# InputAmplifier.net
KiCad netlist of a schematic drawn in Altium Designer
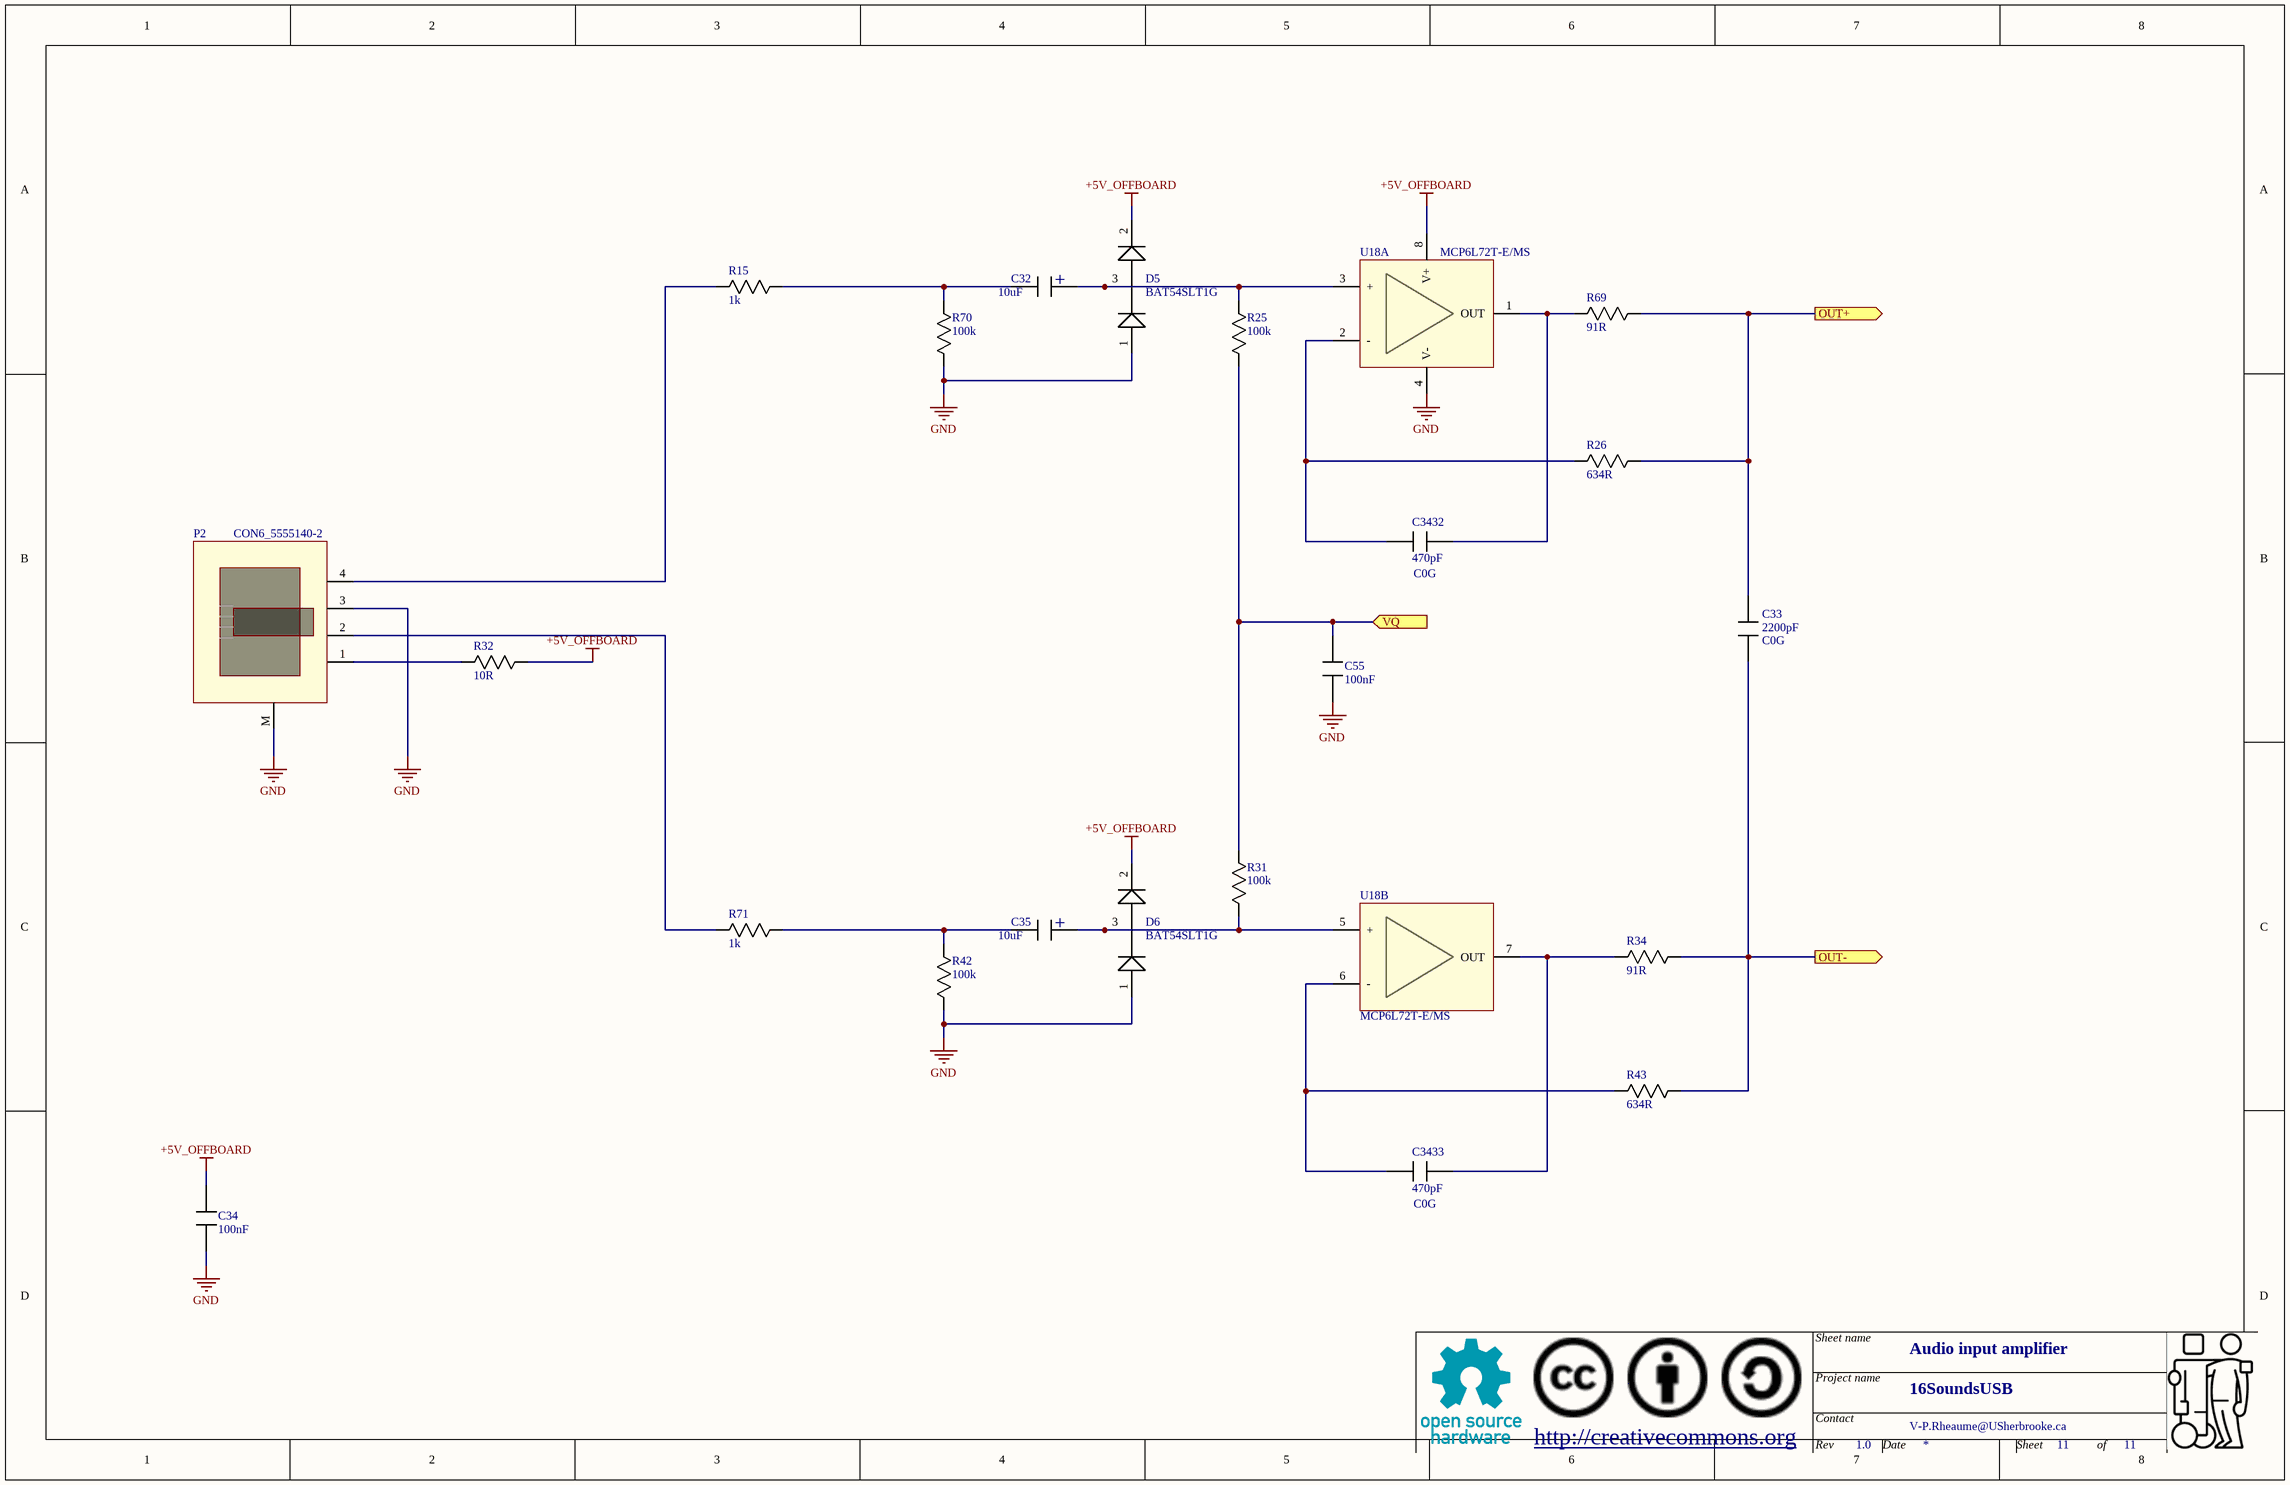
[diagram p0: InputAmplifier.SchDoc]

(export (version "E")
  (design (tool "Eeschema 10.0.6"))
  (components
    (comp (ref "C32")
      (value "10uF")
      (footprint "CAP_RAD_SMD_DIA157")
      (description "Capacitor")
      (fields (field (name "MFG") "Nichicon") (field (name "Comment") "Capacitor_Polarized"))
      (libsource (lib "INTER_2014") (part "Capacitor_Polarized"))
    )
    (comp (ref "C33")
      (value "2200pF")
      (footprint "0603")
      (description "Capacitor")
      (fields (field (name "MFG") "Murata") (field (name "TYPE") "C0G"))
      (libsource (lib "INTER_2014") (part "Capacitor"))
    )
    (comp (ref "C34")
      (value "100nF")
      (footprint "0603")
      (description "Capacitor")
      (fields (field (name "MFG") "Samsung"))
      (libsource (lib "INTER_2014") (part "Capacitor"))
    )
    (comp (ref "C35")
      (value "10uF")
      (footprint "CAP_RAD_SMD_DIA157")
      (description "Capacitor")
      (fields (field (name "MFG") "Nichicon") (field (name "Comment") "Capacitor_Polarized"))
      (libsource (lib "INTER_2014") (part "Capacitor_Polarized"))
    )
    (comp (ref "C55")
      (value "100nF")
      (footprint "0603")
      (description "Capacitor")
      (fields (field (name "MFG") "Samsung"))
      (libsource (lib "INTER_2014") (part "Capacitor"))
    )
    (comp (ref "C3432")
      (value "470pF")
      (footprint "0603")
      (description "Capacitor")
      (fields (field (name "MFG") "Samsung") (field (name "TYPE") "C0G"))
      (libsource (lib "INTER_2014") (part "Capacitor"))
    )
    (comp (ref "C3433")
      (value "470pF")
      (footprint "0603")
      (description "Capacitor")
      (fields (field (name "MFG") "Samsung") (field (name "TYPE") "C0G"))
      (libsource (lib "INTER_2014") (part "Capacitor"))
    )
    (comp (ref "D5")
      (value "Diode_dual")
      (footprint "SOT23_132")
      (description "Diode")
      (fields (field (name "MFG") "Onsemi") (field (name "MFG_PN") "BAT54SLT1G"))
      (libsource (lib "INTER_2014") (part "Diode_dual"))
    )
    (comp (ref "D6")
      (value "Diode_dual")
      (footprint "SOT23_132")
      (description "Diode")
      (fields (field (name "MFG") "Onsemi") (field (name "MFG_PN") "BAT54SLT1G"))
      (libsource (lib "INTER_2014") (part "Diode_dual"))
    )
    (comp (ref "P2")
      (value "CON6_5555140-2")
      (footprint "CONN4_5555140-2")
      (description "6p4c RJ11/RJ14, shielded (5555165-2 unshielded)")
      (fields (field (name "MFG") "TE"))
      (libsource (lib "INTER_2014") (part "CON6_5555140-2"))
    )
    (comp (ref "R15")
      (value "1k")
      (footprint "0603")
      (description "Resistor")
      (fields (field (name "MFG") "Yageo"))
      (libsource (lib "INTER_2014") (part "Resistor"))
    )
    (comp (ref "R25")
      (value "100k")
      (footprint "0603")
      (description "Resistor")
      (fields (field (name "MFG") "Yageo"))
      (libsource (lib "INTER_2014") (part "Resistor"))
    )
    (comp (ref "R26")
      (value "634R")
      (footprint "0603")
      (description "Resistor")
      (fields (field (name "MFG") "Yageo"))
      (libsource (lib "INTER_2014") (part "Resistor"))
    )
    (comp (ref "R31")
      (value "100k")
      (footprint "0603")
      (description "Resistor")
      (fields (field (name "MFG") "Yageo"))
      (libsource (lib "INTER_2014") (part "Resistor"))
    )
    (comp (ref "R32")
      (value "10R")
      (footprint "0603")
      (description "Resistor")
      (fields (field (name "MFG") "Yageo"))
      (libsource (lib "INTER_2014") (part "Resistor"))
    )
    (comp (ref "R34")
      (value "91R")
      (footprint "0603")
      (description "Resistor")
      (fields (field (name "MFG") "Yageo"))
      (libsource (lib "INTER_2014") (part "Resistor"))
    )
    (comp (ref "R42")
      (value "100k")
      (footprint "0603")
      (description "Resistor")
      (fields (field (name "MFG") "Yageo"))
      (libsource (lib "INTER_2014") (part "Resistor"))
    )
    (comp (ref "R43")
      (value "634R")
      (footprint "0603")
      (description "Resistor")
      (fields (field (name "MFG") "Yageo"))
      (libsource (lib "INTER_2014") (part "Resistor"))
    )
    (comp (ref "R69")
      (value "91R")
      (footprint "0603")
      (description "Resistor")
      (fields (field (name "MFG") "Yageo"))
      (libsource (lib "INTER_2014") (part "Resistor"))
    )
    (comp (ref "R70")
      (value "100k")
      (footprint "0603")
      (description "Resistor")
      (fields (field (name "MFG") "Yageo"))
      (libsource (lib "INTER_2014") (part "Resistor"))
    )
    (comp (ref "R71")
      (value "1k")
      (footprint "0603")
      (description "Resistor")
      (fields (field (name "MFG") "Yageo"))
      (libsource (lib "INTER_2014") (part "Resistor"))
    )
    (comp (ref "U18")
      (value "OPA_DUAL")
      (footprint "SOP127P600-8N")
      (description "Dual amplifier (standard)")
      (fields (field (name "MFG") "Microchip") (field (name "MFG_PN") "MCP6L72T-E/MS"))
      (libsource (lib "INTER_2014") (part "OPA_DUAL"))
    )
  )
  (nets
    (net (code "1") (name "+5V_OFFBOARD") (class "Default")
      (node (ref "C34") (pin "1") (pintype "passive"))
      (node (ref "D5") (pin "2") (pinfunction "K_2") (pintype "passive"))
      (node (ref "D6") (pin "2") (pinfunction "K_2") (pintype "passive"))
      (node (ref "R32") (pin "2") (pintype "passive"))
      (node (ref "U18") (pin "8") (pinfunction "V+_8") (pintype "passive"))
    )
    (net (code "2") (name "/OUT+") (class "Default")
      (node (ref "C33") (pin "1") (pintype "passive"))
      (node (ref "R26") (pin "2") (pintype "passive"))
      (node (ref "R69") (pin "2") (pintype "passive"))
    )
    (net (code "3") (name "/OUT-") (class "Default")
      (node (ref "C33") (pin "2") (pintype "passive"))
      (node (ref "R34") (pin "2") (pintype "passive"))
      (node (ref "R43") (pin "2") (pintype "passive"))
    )
    (net (code "4") (name "/VQ") (class "Default")
      (node (ref "C55") (pin "1") (pintype "passive"))
      (node (ref "R25") (pin "1") (pintype "passive"))
      (node (ref "R31") (pin "2") (pintype "passive"))
    )
    (net (code "5") (name "GND") (class "Default")
      (node (ref "C34") (pin "2") (pintype "passive"))
      (node (ref "C55") (pin "2") (pintype "passive"))
      (node (ref "D5") (pin "1") (pinfunction "K_1") (pintype "passive"))
      (node (ref "D6") (pin "1") (pinfunction "K_1") (pintype "passive"))
      (node (ref "P2") (pin "3") (pintype "passive"))
      (node (ref "P2") (pin "M") (pintype "passive"))
      (node (ref "R42") (pin "1") (pintype "passive"))
      (node (ref "R70") (pin "1") (pintype "passive"))
      (node (ref "U18") (pin "4") (pinfunction "V-_4") (pintype "passive"))
    )
    (net (code "6") (name "Net-(C32-Pad-)") (class "Default")
      (node (ref "C32") (pin "-") (pintype "passive"))
      (node (ref "R15") (pin "2") (pintype "passive"))
      (node (ref "R70") (pin "2") (pintype "passive"))
    )
    (net (code "7") (name "Net-(C35-Pad-)") (class "Default")
      (node (ref "C35") (pin "-") (pintype "passive"))
      (node (ref "R42") (pin "2") (pintype "passive"))
      (node (ref "R71") (pin "2") (pintype "passive"))
    )
    (net (code "8") (name "Net-(D5-AK)") (class "Default")
      (node (ref "C32") (pin "+") (pintype "passive"))
      (node (ref "D5") (pin "3") (pinfunction "AK_3") (pintype "passive"))
      (node (ref "R25") (pin "2") (pintype "passive"))
      (node (ref "U18") (pin "3") (pinfunction "+_3") (pintype "passive"))
    )
    (net (code "9") (name "Net-(D6-AK)") (class "Default")
      (node (ref "C35") (pin "+") (pintype "passive"))
      (node (ref "D6") (pin "3") (pinfunction "AK_3") (pintype "passive"))
      (node (ref "R31") (pin "1") (pintype "passive"))
      (node (ref "U18") (pin "5") (pinfunction "+_5") (pintype "passive"))
    )
    (net (code "10") (name "Net-(P2-Pad1)") (class "Default")
      (node (ref "P2") (pin "1") (pintype "passive"))
      (node (ref "R32") (pin "1") (pintype "passive"))
    )
    (net (code "11") (name "Net-(P2-Pad2)") (class "Default")
      (node (ref "P2") (pin "2") (pintype "passive"))
      (node (ref "R71") (pin "1") (pintype "passive"))
    )
    (net (code "12") (name "Net-(P2-Pad4)") (class "Default")
      (node (ref "P2") (pin "4") (pintype "passive"))
      (node (ref "R15") (pin "1") (pintype "passive"))
    )
    (net (code "13") (name "Net-(U18A--)") (class "Default")
      (node (ref "C3432") (pin "1") (pintype "passive"))
      (node (ref "R26") (pin "1") (pintype "passive"))
      (node (ref "U18") (pin "2") (pinfunction "-_2") (pintype "passive"))
    )
    (net (code "14") (name "Net-(U18A-OUT)") (class "Default")
      (node (ref "C3432") (pin "2") (pintype "passive"))
      (node (ref "R69") (pin "1") (pintype "passive"))
      (node (ref "U18") (pin "1") (pinfunction "OUT_1") (pintype "passive"))
    )
    (net (code "15") (name "Net-(U18B--)") (class "Default")
      (node (ref "C3433") (pin "1") (pintype "passive"))
      (node (ref "R43") (pin "1") (pintype "passive"))
      (node (ref "U18") (pin "6") (pinfunction "-_6") (pintype "passive"))
    )
    (net (code "16") (name "Net-(U18B-OUT)") (class "Default")
      (node (ref "C3433") (pin "2") (pintype "passive"))
      (node (ref "R34") (pin "1") (pintype "passive"))
      (node (ref "U18") (pin "7") (pinfunction "OUT_7") (pintype "passive"))
    )
  )
)
